# 04_-_Sensors.net
KiCad netlist of a schematic drawn in Altium Designer
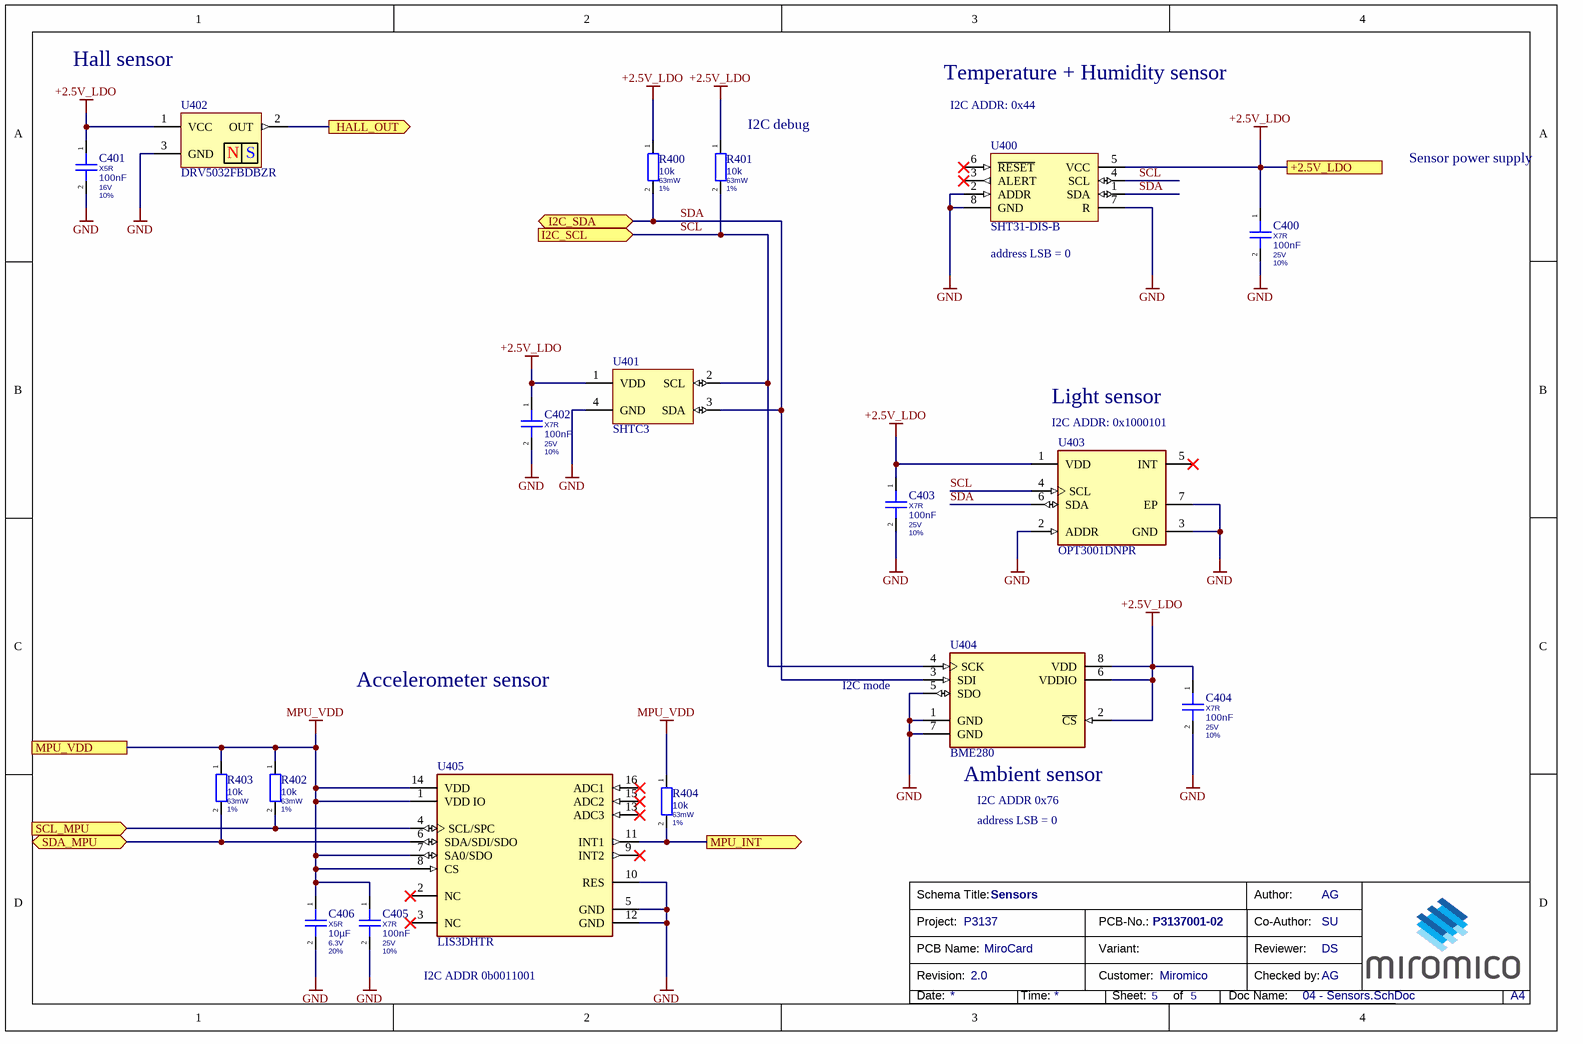
[diagram p0: 04 - Sensors.SchDoc]

(export (version "E")
  (design (tool "Eeschema 10.0.6"))
  (components
    (comp (ref "C400")
      (value "GRM155R71E104KE14J")
      (footprint "CAPC0402(1005)60_L")
      (description "0.1µF ±10% 25V Ceramic Capacitor X7R 0402 (1005 Metric)")
      (fields
        (field (name "DIELECTRIC") "X7R")
        (field (name "CAPACITANCE") "100nF")
        (field (name "VOLTAGE RATING") "25V")
        (field (name "TOLERANCE") "10%")
        (field (name "MANUFACTURER") "Murata Electronics")
      )
      (libsource (lib "Altium Vault Miromico") (part "=Capacitance"))
    )
    (comp (ref "C401")
      (value "GRM155R61C104KA88D")
      (footprint "CAPC0402(1005)60_L")
      (description "0.1µF ±10% 16V Ceramic Capacitor X5R 0402 (1005 Metric)")
      (fields
        (field (name "DIELECTRIC") "X5R")
        (field (name "CAPACITANCE") "100nF")
        (field (name "VOLTAGE RATING") "16V")
        (field (name "TOLERANCE") "10%")
        (field (name "MANUFACTURER") "Murata Electronics")
        (field (name "VOLTAGE") "16V")
      )
      (libsource (lib "Altium Vault Miromico") (part "=Capacitance"))
    )
    (comp (ref "C402")
      (value "GRM155R71E104KE14J")
      (footprint "CAPC0402(1005)60_L")
      (description "0.1µF ±10% 25V Ceramic Capacitor X7R 0402 (1005 Metric)")
      (fields
        (field (name "DIELECTRIC") "X7R")
        (field (name "CAPACITANCE") "100nF")
        (field (name "VOLTAGE RATING") "25V")
        (field (name "TOLERANCE") "10%")
        (field (name "MANUFACTURER") "Murata Electronics")
      )
      (libsource (lib "Altium Vault Miromico") (part "=Capacitance"))
    )
    (comp (ref "C403")
      (value "GRM155R71E104KE14J")
      (footprint "CAPC0402(1005)60_L")
      (description "0.1µF ±10% 25V Ceramic Capacitor X7R 0402 (1005 Metric)")
      (fields
        (field (name "DIELECTRIC") "X7R")
        (field (name "CAPACITANCE") "100nF")
        (field (name "VOLTAGE RATING") "25V")
        (field (name "TOLERANCE") "10%")
        (field (name "MANUFACTURER") "Murata Electronics")
      )
      (libsource (lib "Altium Vault Miromico") (part "=Capacitance"))
    )
    (comp (ref "C404")
      (value "GRM155R71E104KE14J")
      (footprint "CAPC0402(1005)60_L")
      (description "0.1µF ±10% 25V Ceramic Capacitor X7R 0402 (1005 Metric)")
      (fields
        (field (name "DIELECTRIC") "X7R")
        (field (name "CAPACITANCE") "100nF")
        (field (name "VOLTAGE RATING") "25V")
        (field (name "TOLERANCE") "10%")
        (field (name "MANUFACTURER") "Murata Electronics")
      )
      (libsource (lib "Altium Vault Miromico") (part "=Capacitance"))
    )
    (comp (ref "C405")
      (value "GRM155R71E104KE14J")
      (footprint "CAPC0402(1005)60_L")
      (description "0.1µF ±10% 25V Ceramic Capacitor X7R 0402 (1005 Metric)")
      (fields
        (field (name "DIELECTRIC") "X7R")
        (field (name "CAPACITANCE") "100nF")
        (field (name "VOLTAGE RATING") "25V")
        (field (name "TOLERANCE") "10%")
        (field (name "MANUFACTURER") "Murata Electronics")
      )
      (libsource (lib "Altium Vault Miromico") (part "=Capacitance"))
    )
    (comp (ref "C406")
      (value "GRJ155R60J106ME11D")
      (footprint "CAPC0402(1005)60_L")
      (description "10µF ±20% 6.3V Ceramic Capacitor X5R 0402 (1005 Metric)")
      (fields
        (field (name "DIELECTRIC") "X5R")
        (field (name "CAPACITANCE") "10µF")
        (field (name "VOLTAGE RATING") "6.3V")
        (field (name "TOLERANCE") "20%")
        (field (name "MANUFACTURER") "Murata Electronics")
      )
      (libsource (lib "Altium Vault Miromico") (part "=Capacitance"))
    )
    (comp (ref "R400")
      (value "AC0402FR-0710KL")
      (footprint "RESC0201(0603)_L")
      (fields
        (field (name "RESISTANCE") "10k")
        (field (name "POWER RATING") "63mW")
        (field (name "TOLERANCE") "1%")
        (field (name "MANUFACTURER") "Yageo")
      )
      (libsource (lib "Altium Vault Miromico") (part "=Resistance"))
    )
    (comp (ref "R401")
      (value "AC0402FR-0710KL")
      (footprint "RESC0201(0603)_L")
      (fields
        (field (name "RESISTANCE") "10k")
        (field (name "POWER RATING") "63mW")
        (field (name "TOLERANCE") "1%")
        (field (name "MANUFACTURER") "Yageo")
      )
      (libsource (lib "Altium Vault Miromico") (part "=Resistance"))
    )
    (comp (ref "R402")
      (value "AC0402FR-0710KL")
      (footprint "RESC0201(0603)_L")
      (fields
        (field (name "RESISTANCE") "10k")
        (field (name "POWER RATING") "63mW")
        (field (name "TOLERANCE") "1%")
        (field (name "MANUFACTURER") "Yageo")
      )
      (libsource (lib "Altium Vault Miromico") (part "=Resistance"))
    )
    (comp (ref "R403")
      (value "AC0402FR-0710KL")
      (footprint "RESC0201(0603)_L")
      (fields
        (field (name "RESISTANCE") "10k")
        (field (name "POWER RATING") "63mW")
        (field (name "TOLERANCE") "1%")
        (field (name "MANUFACTURER") "Yageo")
      )
      (libsource (lib "Altium Vault Miromico") (part "=Resistance"))
    )
    (comp (ref "R404")
      (value "AC0402FR-0710KL")
      (footprint "RESC0201(0603)_L")
      (fields
        (field (name "RESISTANCE") "10k")
        (field (name "POWER RATING") "63mW")
        (field (name "TOLERANCE") "1%")
        (field (name "MANUFACTURER") "Yageo")
      )
      (libsource (lib "Altium Vault Miromico") (part "=Resistance"))
    )
    (comp (ref "U400")
      (value "SHT31-DIS-B")
      (footprint "8  -  Pin DFN 2.5  x  2.5  mm x 0.9 mm")
      (fields (field (name "MANUFACTURER") "Sensirion"))
      (libsource (lib "Altium Vault Miromico") (part "SHT3x-DIS-x"))
    )
    (comp (ref "U401")
      (value "SHTC3")
      (footprint "SHTC1-Footprint-1")
      (description "SENSOR HUMI/TEMP I2C 2% SMD")
      (fields (field (name "MANUFACTURER") "Sensirion"))
      (libsource (lib "Altium Vault Miromico") (part "SHTC3"))
    )
    (comp (ref "U402")
      (value "DRV5032FBDBZR")
      (footprint "SOT23-3")
      (description "HAL SENSOR, ULTRA-LOW POWER, 1.65V TO 5.5V")
      (fields (field (name "MANUFACTURER") "Texas Instruments"))
      (libsource (lib "Altium Vault Miromico") (part "DRV5032DUDBZT"))
    )
    (comp (ref "U403")
      (value "OPT3001DNPR")
      (footprint "FP-DNP0006A-MFG")
      (description "SENSOR OPT 550NM AMBIENT 6USON")
      (fields
        (field (name "OCTOPART") "https://octopart.com/opt3001dnpr-texas+instruments-47324050")
        (field (name "MANUFACTURER") "Texas Instruments")
      )
      (libsource (lib "Altium Content Vault") (part "6d36863dc75c3adee7e1b5a0d97a822"))
    )
    (comp (ref "U404")
      (value "BME280")
      (footprint "FP-BME280-MFG")
      (description "SENSOR PRESSURE HUMIDITY TEMP")
      (libsource (lib "Altium Content Vault") (part "0dc00059c2188b5fe1feb3ffa9c2262"))
    )
    (comp (ref "U405")
      (value "LIS3DHTR")
      (footprint "FP-LGA-16-7983231-MFG")
      (description "ACCEL 2-16G I2C/SPI 16LGA")
      (libsource (lib "Altium Content Vault") (part "e01d1e8c1555843447ca06cf79c9d9f"))
    )
  )
  (nets
    (net (code "1") (name "+2.5V_LDO") (class "Default")
      (node (ref "C400") (pin "1") (pinfunction "1_1") (pintype "passive"))
      (node (ref "C401") (pin "1") (pinfunction "1_1") (pintype "passive"))
      (node (ref "C402") (pin "1") (pinfunction "1_1") (pintype "passive"))
      (node (ref "C403") (pin "1") (pinfunction "1_1") (pintype "passive"))
      (node (ref "C404") (pin "1") (pinfunction "1_1") (pintype "passive"))
      (node (ref "R400") (pin "1") (pinfunction "1_1") (pintype "passive"))
      (node (ref "R401") (pin "1") (pinfunction "1_1") (pintype "passive"))
      (node (ref "U400") (pin "5") (pinfunction "VCC_5") (pintype "power_in"))
      (node (ref "U401") (pin "1") (pinfunction "VDD_1") (pintype "power_in"))
      (node (ref "U402") (pin "1") (pinfunction "VCC_1") (pintype "power_in"))
      (node (ref "U403") (pin "1") (pinfunction "VDD_1") (pintype "power_in"))
      (node (ref "U404") (pin "2") (pinfunction "~{CS}_2") (pintype "input"))
      (node (ref "U404") (pin "6") (pinfunction "VDDIO_6") (pintype "power_in"))
      (node (ref "U404") (pin "8") (pinfunction "VDD_8") (pintype "power_in"))
    )
    (net (code "2") (name "/HALL_OUT") (class "Default")
      (node (ref "U402") (pin "2") (pinfunction "OUT_2") (pintype "output"))
    )
    (net (code "3") (name "/MPU_INT") (class "Default")
      (node (ref "R404") (pin "2") (pinfunction "2_2") (pintype "passive"))
      (node (ref "U405") (pin "11") (pinfunction "INT1_11") (pintype "output"))
    )
    (net (code "4") (name "/SCL") (class "Default")
      (node (ref "R401") (pin "2") (pinfunction "2_2") (pintype "passive"))
      (node (ref "U400") (pin "4") (pinfunction "SCL_4") (pintype "bidirectional"))
      (node (ref "U401") (pin "2") (pinfunction "SCL_2") (pintype "bidirectional"))
      (node (ref "U403") (pin "4") (pinfunction "SCL_4") (pintype "input"))
      (node (ref "U404") (pin "4") (pinfunction "SCK_4") (pintype "input"))
    )
    (net (code "5") (name "/SCL_MPU") (class "Default")
      (node (ref "R402") (pin "2") (pinfunction "2_2") (pintype "passive"))
      (node (ref "U405") (pin "4") (pinfunction "SCL/SPC_4") (pintype "bidirectional"))
    )
    (net (code "6") (name "/SDA") (class "Default")
      (node (ref "R400") (pin "2") (pinfunction "2_2") (pintype "passive"))
      (node (ref "U400") (pin "1") (pinfunction "SDA_1") (pintype "bidirectional"))
      (node (ref "U401") (pin "3") (pinfunction "SDA_3") (pintype "bidirectional"))
      (node (ref "U403") (pin "6") (pinfunction "SDA_6") (pintype "bidirectional"))
      (node (ref "U404") (pin "3") (pinfunction "SDI_3") (pintype "input"))
    )
    (net (code "7") (name "/SDA_MPU") (class "Default")
      (node (ref "R403") (pin "2") (pinfunction "2_2") (pintype "passive"))
      (node (ref "U405") (pin "6") (pinfunction "SDA/SDI/SDO_6") (pintype "bidirectional"))
    )
    (net (code "8") (name "GND") (class "Default")
      (node (ref "C400") (pin "2") (pinfunction "2_2") (pintype "passive"))
      (node (ref "C401") (pin "2") (pinfunction "2_2") (pintype "passive"))
      (node (ref "C402") (pin "2") (pinfunction "2_2") (pintype "passive"))
      (node (ref "C403") (pin "2") (pinfunction "2_2") (pintype "passive"))
      (node (ref "C404") (pin "2") (pinfunction "2_2") (pintype "passive"))
      (node (ref "C405") (pin "2") (pinfunction "2_2") (pintype "passive"))
      (node (ref "C406") (pin "2") (pinfunction "2_2") (pintype "passive"))
      (node (ref "U400") (pin "2") (pinfunction "ADDR_2") (pintype "input"))
      (node (ref "U400") (pin "7") (pinfunction "R_7") (pintype "power_in"))
      (node (ref "U400") (pin "8") (pinfunction "GND_8") (pintype "power_in"))
      (node (ref "U401") (pin "4") (pinfunction "GND_4") (pintype "power_in"))
      (node (ref "U402") (pin "3") (pinfunction "GND_3") (pintype "power_in"))
      (node (ref "U403") (pin "2") (pinfunction "ADDR_2") (pintype "input"))
      (node (ref "U403") (pin "3") (pinfunction "GND_3") (pintype "power_in"))
      (node (ref "U403") (pin "7") (pinfunction "EP_7") (pintype "power_in"))
      (node (ref "U404") (pin "1") (pinfunction "GND_1") (pintype "power_in"))
      (node (ref "U404") (pin "5") (pinfunction "SDO_5") (pintype "bidirectional"))
      (node (ref "U404") (pin "7") (pinfunction "GND_7") (pintype "power_in"))
      (node (ref "U405") (pin "10") (pinfunction "RES_10") (pintype "power_in"))
      (node (ref "U405") (pin "12") (pinfunction "GND_12") (pintype "power_in"))
      (node (ref "U405") (pin "5") (pinfunction "GND_5") (pintype "power_in"))
    )
    (net (code "9") (name "MPU_VDD") (class "Default")
      (node (ref "C405") (pin "1") (pinfunction "1_1") (pintype "passive"))
      (node (ref "C406") (pin "1") (pinfunction "1_1") (pintype "passive"))
      (node (ref "R402") (pin "1") (pinfunction "1_1") (pintype "passive"))
      (node (ref "R403") (pin "1") (pinfunction "1_1") (pintype "passive"))
      (node (ref "R404") (pin "1") (pinfunction "1_1") (pintype "passive"))
      (node (ref "U405") (pin "1") (pinfunction "VDD_IO_1") (pintype "power_in"))
      (node (ref "U405") (pin "14") (pinfunction "VDD_14") (pintype "power_in"))
      (node (ref "U405") (pin "7") (pinfunction "SA0/SDO_7") (pintype "bidirectional"))
      (node (ref "U405") (pin "8") (pinfunction "CS_8") (pintype "input"))
    )
    (net (code "10") (name "unconnected-(U400-ALERT-Pad3)") (class "Default")
      (node (ref "U400") (pin "3") (pinfunction "ALERT_3") (pintype "output+no_connect"))
    )
    (net (code "11") (name "unconnected-(U400-~{RESET}-Pad6)") (class "Default")
      (node (ref "U400") (pin "6") (pinfunction "~{RESET}_6") (pintype "input+no_connect"))
    )
    (net (code "12") (name "unconnected-(U403-INT-Pad5)") (class "Default")
      (node (ref "U403") (pin "5") (pinfunction "INT_5") (pintype "open_collector+no_connect"))
    )
    (net (code "13") (name "unconnected-(U405-ADC1-Pad16)") (class "Default")
      (node (ref "U405") (pin "16") (pinfunction "ADC1_16") (pintype "input+no_connect"))
    )
    (net (code "14") (name "unconnected-(U405-ADC2-Pad15)") (class "Default")
      (node (ref "U405") (pin "15") (pinfunction "ADC2_15") (pintype "input+no_connect"))
    )
    (net (code "15") (name "unconnected-(U405-ADC3-Pad13)") (class "Default")
      (node (ref "U405") (pin "13") (pinfunction "ADC3_13") (pintype "input+no_connect"))
    )
    (net (code "16") (name "unconnected-(U405-INT2-Pad9)") (class "Default")
      (node (ref "U405") (pin "9") (pinfunction "INT2_9") (pintype "output+no_connect"))
    )
    (net (code "17") (name "unconnected-(U405-NC-Pad2)") (class "Default")
      (node (ref "U405") (pin "2") (pinfunction "NC_2") (pintype "passive+no_connect"))
    )
    (net (code "18") (name "unconnected-(U405-NC-Pad3)") (class "Default")
      (node (ref "U405") (pin "3") (pinfunction "NC_3") (pintype "passive+no_connect"))
    )
  )
)
